# E6_main.net
KiCad netlist of a schematic drawn in EAGLE
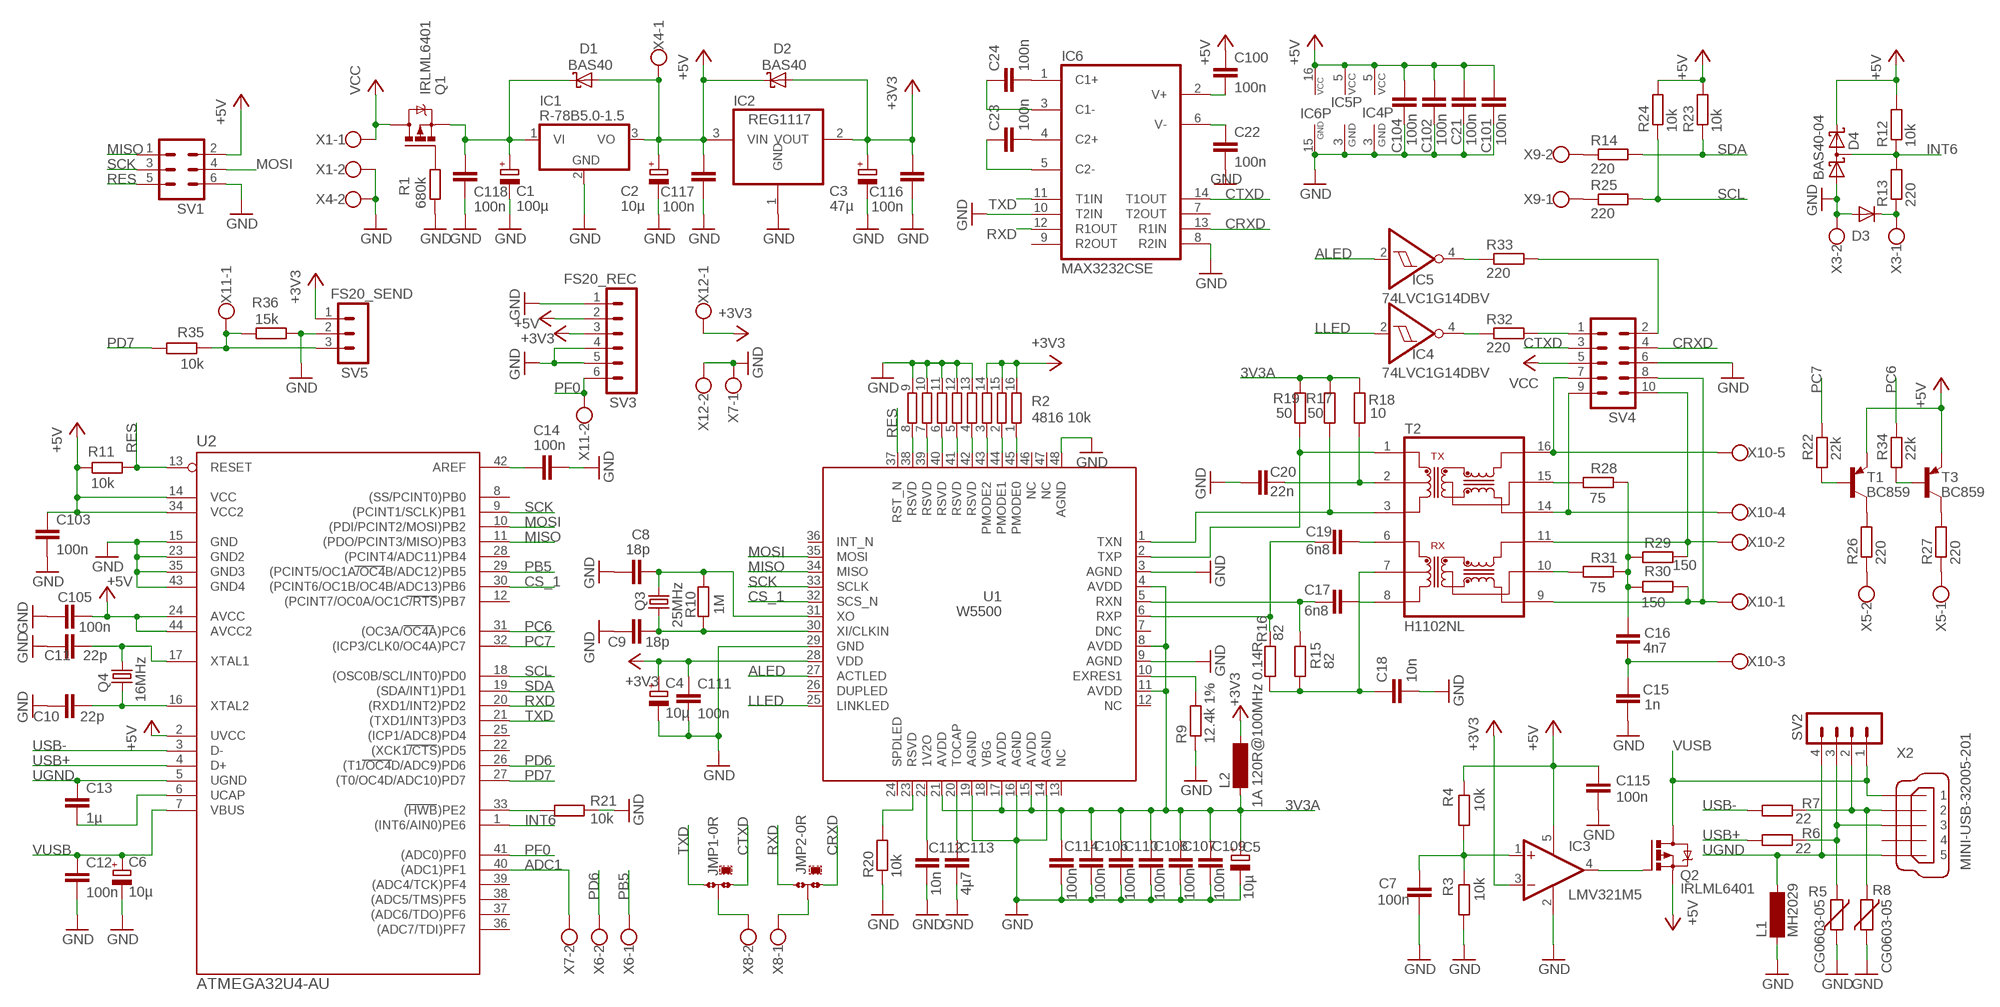
[diagram p0: schematic, sheet 1]

(export (version "E")
  (design (tool "Eeschema 10.0.6"))
  (components
    (comp (ref "C1")
      (value "100µ")
      (footprint "eagle-import:E2,5-7")
      (libsource (lib "eagle-import") (part "CPOL-EUE2.5-7"))
    )
    (comp (ref "C2")
      (value "10µ")
      (footprint "eagle-import:E2-5")
      (libsource (lib "eagle-import") (part "CPOL-EUE2-5"))
    )
    (comp (ref "C3")
      (value "47µ")
      (footprint "eagle-import:E2-5")
      (libsource (lib "eagle-import") (part "CPOL-EUE2-5"))
    )
    (comp (ref "C4")
      (value "10µ")
      (footprint "eagle-import:E2-5")
      (libsource (lib "eagle-import") (part "CPOL-EUE2-5"))
    )
    (comp (ref "C5")
      (value "10µ")
      (footprint "eagle-import:E2-5")
      (libsource (lib "eagle-import") (part "CPOL-EUE2-5"))
    )
    (comp (ref "C6")
      (value "10µ")
      (footprint "eagle-import:E2-5")
      (libsource (lib "eagle-import") (part "CPOL-EUE2-5"))
    )
    (comp (ref "C7")
      (value "100n")
      (footprint "eagle-import:C0805K")
      (libsource (lib "eagle-import") (part "C-EUC0805K"))
    )
    (comp (ref "C8")
      (value "18p")
      (footprint "eagle-import:C0805K")
      (libsource (lib "eagle-import") (part "C-EUC0805K"))
    )
    (comp (ref "C9")
      (value "18p")
      (footprint "eagle-import:C0805K")
      (libsource (lib "eagle-import") (part "C-EUC0805K"))
    )
    (comp (ref "C10")
      (value "22p")
      (footprint "eagle-import:C0805K")
      (libsource (lib "eagle-import") (part "C-EUC0805K"))
    )
    (comp (ref "C11")
      (value "22p")
      (footprint "eagle-import:C0805K")
      (libsource (lib "eagle-import") (part "C-EUC0805K"))
    )
    (comp (ref "C12")
      (value "100n")
      (footprint "eagle-import:C0805K")
      (libsource (lib "eagle-import") (part "C-EUC0805K"))
    )
    (comp (ref "C13")
      (value "1µ")
      (footprint "eagle-import:C0805K")
      (libsource (lib "eagle-import") (part "C-EUC0805K"))
    )
    (comp (ref "C14")
      (value "100n")
      (footprint "eagle-import:C0805K")
      (libsource (lib "eagle-import") (part "C-EUC0805K"))
    )
    (comp (ref "C15")
      (value "1n")
      (footprint "eagle-import:C0805K")
      (libsource (lib "eagle-import") (part "C-EUC0805K"))
    )
    (comp (ref "C16")
      (value "4n7")
      (footprint "eagle-import:C0805K")
      (libsource (lib "eagle-import") (part "C-EUC0805K"))
    )
    (comp (ref "C17")
      (value "6n8")
      (footprint "eagle-import:C0805K")
      (libsource (lib "eagle-import") (part "C-EUC0805K"))
    )
    (comp (ref "C18")
      (value "10n")
      (footprint "eagle-import:C0805K")
      (libsource (lib "eagle-import") (part "C-EUC0805K"))
    )
    (comp (ref "C19")
      (value "6n8")
      (footprint "eagle-import:C0805K")
      (libsource (lib "eagle-import") (part "C-EUC0805K"))
    )
    (comp (ref "C20")
      (value "22n")
      (footprint "eagle-import:C0805K")
      (libsource (lib "eagle-import") (part "C-EUC0805K"))
    )
    (comp (ref "C21")
      (value "100n")
      (footprint "eagle-import:C0805K")
      (libsource (lib "eagle-import") (part "C-EUC0805K"))
    )
    (comp (ref "C22")
      (value "100n")
      (footprint "eagle-import:C0805K")
      (libsource (lib "eagle-import") (part "C-EUC0805K"))
    )
    (comp (ref "C23")
      (value "100n")
      (footprint "eagle-import:C0805K")
      (libsource (lib "eagle-import") (part "C-EUC0805K"))
    )
    (comp (ref "C24")
      (value "100n")
      (footprint "eagle-import:C0805K")
      (libsource (lib "eagle-import") (part "C-EUC0805K"))
    )
    (comp (ref "C100")
      (value "100n")
      (footprint "eagle-import:C0805K")
      (libsource (lib "eagle-import") (part "C-EUC0805K"))
    )
    (comp (ref "C101")
      (value "100n")
      (footprint "eagle-import:C0805K")
      (libsource (lib "eagle-import") (part "C-EUC0805K"))
    )
    (comp (ref "C102")
      (value "100n")
      (footprint "eagle-import:C0805K")
      (libsource (lib "eagle-import") (part "C-EUC0805K"))
    )
    (comp (ref "C103")
      (value "100n")
      (footprint "eagle-import:C0805K")
      (libsource (lib "eagle-import") (part "C-EUC0805K"))
    )
    (comp (ref "C104")
      (value "100n")
      (footprint "eagle-import:C0805K")
      (libsource (lib "eagle-import") (part "C-EUC0805K"))
    )
    (comp (ref "C105")
      (value "100n")
      (footprint "eagle-import:C0805K")
      (libsource (lib "eagle-import") (part "C-EUC0805K"))
    )
    (comp (ref "C106")
      (value "100n")
      (footprint "eagle-import:C0805K")
      (libsource (lib "eagle-import") (part "C-EUC0805K"))
    )
    (comp (ref "C107")
      (value "100n")
      (footprint "eagle-import:C0805K")
      (libsource (lib "eagle-import") (part "C-EUC0805K"))
    )
    (comp (ref "C108")
      (value "100n")
      (footprint "eagle-import:C0805K")
      (libsource (lib "eagle-import") (part "C-EUC0805K"))
    )
    (comp (ref "C109")
      (value "100n")
      (footprint "eagle-import:C0805K")
      (libsource (lib "eagle-import") (part "C-EUC0805K"))
    )
    (comp (ref "C110")
      (value "100n")
      (footprint "eagle-import:C0805K")
      (libsource (lib "eagle-import") (part "C-EUC0805K"))
    )
    (comp (ref "C111")
      (value "100n")
      (footprint "eagle-import:C0805K")
      (libsource (lib "eagle-import") (part "C-EUC0805K"))
    )
    (comp (ref "C112")
      (value "10n")
      (footprint "eagle-import:C0805K")
      (libsource (lib "eagle-import") (part "C-EUC0805K"))
    )
    (comp (ref "C113")
      (value "4µ7")
      (footprint "eagle-import:C0805K")
      (libsource (lib "eagle-import") (part "C-EUC0805K"))
    )
    (comp (ref "C114")
      (value "100n")
      (footprint "eagle-import:C0805K")
      (libsource (lib "eagle-import") (part "C-EUC0805K"))
    )
    (comp (ref "C115")
      (value "100n")
      (footprint "eagle-import:C0805K")
      (libsource (lib "eagle-import") (part "C-EUC0805K"))
    )
    (comp (ref "C116")
      (value "100n")
      (footprint "eagle-import:C0805K")
      (libsource (lib "eagle-import") (part "C-EUC0805K"))
    )
    (comp (ref "C117")
      (value "100n")
      (footprint "eagle-import:C0805K")
      (libsource (lib "eagle-import") (part "C-EUC0805K"))
    )
    (comp (ref "C118")
      (value "100n")
      (footprint "eagle-import:C0805K")
      (libsource (lib "eagle-import") (part "C-EUC0805K"))
    )
    (comp (ref "D1")
      (value "BAS40")
      (footprint "eagle-import:SOT23")
      (libsource (lib "eagle-import") (part "BAS40"))
    )
    (comp (ref "D2")
      (value "BAS40")
      (footprint "eagle-import:SOT23")
      (libsource (lib "eagle-import") (part "BAS40"))
    )
    (comp (ref "D3")
      (value "DIODE-SOT54H")
      (footprint "eagle-import:SOT54H")
      (libsource (lib "eagle-import") (part "DIODE-SOT54H"))
    )
    (comp (ref "D4")
      (value "BAS40-04")
      (footprint "eagle-import:SOT23")
      (libsource (lib "eagle-import") (part "BAS40-04"))
    )
    (comp (ref "IC1")
      (value "R-78B5.0-1.5")
      (footprint "eagle-import:TO220V")
      (libsource (lib "eagle-import") (part "78TV05"))
    )
    (comp (ref "IC2")
      (value "REG1117")
      (footprint "eagle-import:SOT223")
      (libsource (lib "eagle-import") (part "REG1117"))
    )
    (comp (ref "IC3")
      (value "LMV321M5")
      (footprint "eagle-import:SOT23-5")
      (libsource (lib "eagle-import") (part "LMV321?M5"))
    )
    (comp (ref "IC4")
      (value "74LVC1G14DBV")
      (footprint "eagle-import:SOT23-5")
      (libsource (lib "eagle-import") (part "741G14DBVLVC"))
    )
    (comp (ref "IC5")
      (value "74LVC1G14DBV")
      (footprint "eagle-import:SOT23-5")
      (libsource (lib "eagle-import") (part "741G14DBVLVC"))
    )
    (comp (ref "IC6")
      (value "MAX3232CSE")
      (footprint "eagle-import:SO16")
      (libsource (lib "eagle-import") (part "MAX3232SEC"))
    )
    (comp (ref "JMP1")
      (value "0R-JUMPA")
      (footprint "eagle-import:A0R-JMP")
      (libsource (lib "eagle-import") (part "0R-JUMPA"))
    )
    (comp (ref "JMP2")
      (value "0R-JUMPA")
      (footprint "eagle-import:A0R-JMP")
      (libsource (lib "eagle-import") (part "0R-JUMPA"))
    )
    (comp (ref "L1")
      (value "MH2029")
      (footprint "eagle-import:SM-1206")
      (libsource (lib "eagle-import") (part "SM-1206"))
    )
    (comp (ref "L2")
      (value "1A 120R@100MHz 0.14R")
      (footprint "eagle-import:SM-1206")
      (libsource (lib "eagle-import") (part "SM-1206"))
    )
    (comp (ref "Q1")
      (value "IRLML6401")
      (footprint "eagle-import:MICRO3")
      (libsource (lib "eagle-import") (part "IRLML5203"))
    )
    (comp (ref "Q2")
      (value "IRLML6401")
      (footprint "eagle-import:MICRO3")
      (libsource (lib "eagle-import") (part "IRLML5203"))
    )
    (comp (ref "Q3")
      (value "25MHz")
      (footprint "eagle-import:HC49_S")
      (libsource (lib "eagle-import") (part "CRYSTALHC49S"))
    )
    (comp (ref "Q4")
      (value "16MHz")
      (footprint "eagle-import:HC49_S")
      (libsource (lib "eagle-import") (part "CRYSTALHC49S"))
    )
    (comp (ref "R1")
      (value "680k")
      (footprint "eagle-import:R0805")
      (libsource (lib "eagle-import") (part "R-EU_R0805"))
    )
    (comp (ref "R2")
      (value "4816 10k")
      (footprint "eagle-import:4816P")
      (fields (field (name "MF") "BOURNS, INC.") (field (name "MPN") "4816P-T01-684LF"))
      (libsource (lib "eagle-import") (part "4816P-T01"))
    )
    (comp (ref "R3")
      (value "10k")
      (footprint "eagle-import:R0805")
      (libsource (lib "eagle-import") (part "R-EU_R0805"))
    )
    (comp (ref "R4")
      (value "10k")
      (footprint "eagle-import:R0805")
      (libsource (lib "eagle-import") (part "R-EU_R0805"))
    )
    (comp (ref "R5")
      (value "CG0603-05")
      (footprint "eagle-import:CT_CN0603")
      (libsource (lib "eagle-import") (part "VARISTORCN0603"))
    )
    (comp (ref "R6")
      (value "22")
      (footprint "eagle-import:R0805")
      (libsource (lib "eagle-import") (part "R-EU_R0805"))
    )
    (comp (ref "R7")
      (value "22")
      (footprint "eagle-import:R0805")
      (libsource (lib "eagle-import") (part "R-EU_R0805"))
    )
    (comp (ref "R8")
      (value "CG0603-05")
      (footprint "eagle-import:CT_CN0603")
      (libsource (lib "eagle-import") (part "VARISTORCN0603"))
    )
    (comp (ref "R9")
      (value "12.4k 1%")
      (footprint "eagle-import:R0805")
      (libsource (lib "eagle-import") (part "R-EU_R0805"))
    )
    (comp (ref "R10")
      (value "1M")
      (footprint "eagle-import:R0805")
      (libsource (lib "eagle-import") (part "R-EU_R0805"))
    )
    (comp (ref "R11")
      (value "10k")
      (footprint "eagle-import:R0805")
      (libsource (lib "eagle-import") (part "R-EU_R0805"))
    )
    (comp (ref "R12")
      (value "10k")
      (footprint "eagle-import:R0805")
      (libsource (lib "eagle-import") (part "R-EU_R0805"))
    )
    (comp (ref "R13")
      (value "220")
      (footprint "eagle-import:R0805")
      (libsource (lib "eagle-import") (part "R-EU_R0805"))
    )
    (comp (ref "R14")
      (value "220")
      (footprint "eagle-import:R0805")
      (libsource (lib "eagle-import") (part "R-EU_R0805"))
    )
    (comp (ref "R15")
      (value "82")
      (footprint "eagle-import:R0805")
      (libsource (lib "eagle-import") (part "R-EU_R0805"))
    )
    (comp (ref "R16")
      (value "82")
      (footprint "eagle-import:R0805")
      (libsource (lib "eagle-import") (part "R-EU_R0805"))
    )
    (comp (ref "R17")
      (value "50")
      (footprint "eagle-import:R0805")
      (libsource (lib "eagle-import") (part "R-EU_R0805"))
    )
    (comp (ref "R18")
      (value "10")
      (footprint "eagle-import:R0805")
      (libsource (lib "eagle-import") (part "R-EU_R0805"))
    )
    (comp (ref "R19")
      (value "50")
      (footprint "eagle-import:R0805")
      (libsource (lib "eagle-import") (part "R-EU_R0805"))
    )
    (comp (ref "R20")
      (value "10k")
      (footprint "eagle-import:R0805")
      (libsource (lib "eagle-import") (part "R-EU_R0805"))
    )
    (comp (ref "R21")
      (value "10k")
      (footprint "eagle-import:R0805")
      (libsource (lib "eagle-import") (part "R-EU_R0805"))
    )
    (comp (ref "R22")
      (value "22k")
      (footprint "eagle-import:R0805")
      (libsource (lib "eagle-import") (part "R-EU_R0805"))
    )
    (comp (ref "R23")
      (value "10k")
      (footprint "eagle-import:R0805")
      (libsource (lib "eagle-import") (part "R-EU_R0805"))
    )
    (comp (ref "R24")
      (value "10k")
      (footprint "eagle-import:R0805")
      (libsource (lib "eagle-import") (part "R-EU_R0805"))
    )
    (comp (ref "R25")
      (value "220")
      (footprint "eagle-import:R0805")
      (libsource (lib "eagle-import") (part "R-EU_R0805"))
    )
    (comp (ref "R26")
      (value "220")
      (footprint "eagle-import:R0805")
      (libsource (lib "eagle-import") (part "R-EU_R0805"))
    )
    (comp (ref "R27")
      (value "220")
      (footprint "eagle-import:R0805")
      (libsource (lib "eagle-import") (part "R-EU_R0805"))
    )
    (comp (ref "R28")
      (value "75")
      (footprint "eagle-import:R0805")
      (libsource (lib "eagle-import") (part "R-EU_R0805"))
    )
    (comp (ref "R29")
      (value "150")
      (footprint "eagle-import:R0805")
      (libsource (lib "eagle-import") (part "R-EU_R0805"))
    )
    (comp (ref "R30")
      (value "150")
      (footprint "eagle-import:R0805")
      (libsource (lib "eagle-import") (part "R-EU_R0805"))
    )
    (comp (ref "R31")
      (value "75")
      (footprint "eagle-import:R0805")
      (libsource (lib "eagle-import") (part "R-EU_R0805"))
    )
    (comp (ref "R32")
      (value "220")
      (footprint "eagle-import:R0805")
      (libsource (lib "eagle-import") (part "R-EU_R0805"))
    )
    (comp (ref "R33")
      (value "220")
      (footprint "eagle-import:R0805")
      (libsource (lib "eagle-import") (part "R-EU_R0805"))
    )
    (comp (ref "R34")
      (value "22k")
      (footprint "eagle-import:R0805")
      (libsource (lib "eagle-import") (part "R-EU_R0805"))
    )
    (comp (ref "R35")
      (value "10k")
      (footprint "eagle-import:R0805")
      (libsource (lib "eagle-import") (part "R-EU_R0805"))
    )
    (comp (ref "R36")
      (value "15k")
      (footprint "eagle-import:R0805")
      (libsource (lib "eagle-import") (part "R-EU_R0805"))
    )
    (comp (ref "SV1")
      (value "ML6")
      (footprint "eagle-import:ML6")
      (libsource (lib "eagle-import") (part "ML6"))
    )
    (comp (ref "SV2")
      (value "MA04-1")
      (footprint "eagle-import:MA04-1")
      (libsource (lib "eagle-import") (part "MA04-1"))
    )
    (comp (ref "SV3")
      (value "FS20_REC")
      (footprint "eagle-import:MA06-1")
      (libsource (lib "eagle-import") (part "MA06-1"))
    )
    (comp (ref "SV4")
      (value "ML10")
      (footprint "eagle-import:ML10")
      (libsource (lib "eagle-import") (part "ML10"))
    )
    (comp (ref "SV5")
      (value "FS20_SEND")
      (footprint "eagle-import:MA03-1")
      (libsource (lib "eagle-import") (part "MA03-1"))
    )
    (comp (ref "T1")
      (value "BC859")
      (footprint "eagle-import:SOT23-BEC")
      (libsource (lib "eagle-import") (part "-PNP-SOT23-BECBC857A"))
    )
    (comp (ref "T2")
      (value "H1102NL")
      (footprint "eagle-import:HXXXX")
      (libsource (lib "eagle-import") (part "HX1188"))
    )
    (comp (ref "T3")
      (value "BC859")
      (footprint "eagle-import:SOT23-BEC")
      (libsource (lib "eagle-import") (part "-PNP-SOT23-BECBC857A"))
    )
    (comp (ref "U1")
      (value "W5500")
      (footprint "eagle-import:W5500")
      (libsource (lib "eagle-import") (part "W5500"))
    )
    (comp (ref "U2")
      (value "ATMEGA32U4-AU")
      (footprint "eagle-import:TQFP44")
      (libsource (lib "eagle-import") (part "ATMEGA32U4-AU"))
    )
    (comp (ref "X1")
      (value "W237-02P")
      (footprint "eagle-import:W237-132")
      (libsource (lib "eagle-import") (part "W237-02P"))
    )
    (comp (ref "X2")
      (value "MINI-USB-32005-201")
      (footprint "eagle-import:32005-201")
      (libsource (lib "eagle-import") (part "MINI-USB-32005-201"))
    )
    (comp (ref "X3")
      (value "W237-02P")
      (footprint "eagle-import:W237-132")
      (libsource (lib "eagle-import") (part "W237-02P"))
    )
    (comp (ref "X4")
      (value "W237-02P")
      (footprint "eagle-import:W237-132")
      (libsource (lib "eagle-import") (part "W237-02P"))
    )
    (comp (ref "X5")
      (value "W237-02P")
      (footprint "eagle-import:W237-132")
      (libsource (lib "eagle-import") (part "W237-02P"))
    )
    (comp (ref "X6")
      (value "W237-02P")
      (footprint "eagle-import:W237-132")
      (libsource (lib "eagle-import") (part "W237-02P"))
    )
    (comp (ref "X7")
      (value "W237-02P")
      (footprint "eagle-import:W237-132")
      (libsource (lib "eagle-import") (part "W237-02P"))
    )
    (comp (ref "X8")
      (value "W237-02P")
      (footprint "eagle-import:W237-132")
      (libsource (lib "eagle-import") (part "W237-02P"))
    )
    (comp (ref "X9")
      (value "W237-02P")
      (footprint "eagle-import:W237-132")
      (libsource (lib "eagle-import") (part "W237-02P"))
    )
    (comp (ref "X10")
      (value "W237-05P")
      (footprint "eagle-import:W237-5P")
      (libsource (lib "eagle-import") (part "W237-05P"))
    )
    (comp (ref "X11")
      (value "W237-02P")
      (footprint "eagle-import:W237-132")
      (libsource (lib "eagle-import") (part "W237-02P"))
    )
    (comp (ref "X12")
      (value "W237-02P")
      (footprint "eagle-import:W237-132")
      (libsource (lib "eagle-import") (part "W237-02P"))
    )
  )
  (nets
    (net (code "1") (name "+3V3") (class "Default")
      (node (ref "C111") (pin "1") (pinfunction "1_1") (pintype "passive"))
      (node (ref "C116") (pin "2") (pinfunction "2_2") (pintype "passive"))
      (node (ref "C3") (pin "+") (pinfunction "+_+") (pintype "passive"))
      (node (ref "C4") (pin "+") (pinfunction "+_+") (pintype "passive"))
      (node (ref "D2") (pin "1") (pinfunction "A_1") (pintype "passive"))
      (node (ref "IC2") (pin "2") (pinfunction "VOUT_2") (pintype "output"))
      (node (ref "IC3") (pin "3") (pinfunction "-IN_3") (pintype "input"))
      (node (ref "L2") (pin "2") (pinfunction "2_2") (pintype "passive"))
      (node (ref "R2") (pin "14") (pinfunction "14_14") (pintype "passive"))
      (node (ref "R2") (pin "15") (pinfunction "15_15") (pintype "passive"))
      (node (ref "R2") (pin "16") (pinfunction "16_16") (pintype "passive"))
      (node (ref "SV3") (pin "3") (pinfunction "3_3") (pintype "passive"))
      (node (ref "SV5") (pin "1") (pinfunction "1_1") (pintype "passive"))
      (node (ref "U1") (pin "28") (pinfunction "VDD_28") (pintype "passive"))
      (node (ref "X12") (pin "1") (pinfunction "KL_1") (pintype "passive"))
    )
    (net (code "2") (name "+5V") (class "Default")
      (node (ref "C100") (pin "1") (pinfunction "1_1") (pintype "passive"))
      (node (ref "C101") (pin "1") (pinfunction "1_1") (pintype "passive"))
      (node (ref "C102") (pin "2") (pinfunction "2_2") (pintype "passive"))
      (node (ref "C103") (pin "1") (pinfunction "1_1") (pintype "passive"))
      (node (ref "C104") (pin "2") (pinfunction "2_2") (pintype "passive"))
      (node (ref "C105") (pin "1") (pinfunction "1_1") (pintype "passive"))
      (node (ref "C115") (pin "2") (pinfunction "2_2") (pintype "passive"))
      (node (ref "C117") (pin "2") (pinfunction "2_2") (pintype "passive"))
      (node (ref "C2") (pin "+") (pinfunction "+_+") (pintype "passive"))
      (node (ref "C21") (pin "1") (pinfunction "1_1") (pintype "passive"))
      (node (ref "D1") (pin "1") (pinfunction "A_1") (pintype "passive"))
      (node (ref "D2") (pin "3") (pinfunction "C_3") (pintype "passive"))
      (node (ref "D4") (pin "2") (pinfunction "C2_2") (pintype "passive"))
      (node (ref "IC1") (pin "3") (pinfunction "VO_3") (pintype "passive"))
      (node (ref "IC2") (pin "3") (pinfunction "VIN_3") (pintype "input"))
      (node (ref "IC3") (pin "5") (pinfunction "V+_5") (pintype "power_in"))
      (node (ref "IC4") (pin "5") (pinfunction "VCC_5") (pintype "power_in"))
      (node (ref "IC5") (pin "5") (pinfunction "VCC_5") (pintype "power_in"))
      (node (ref "IC6") (pin "16") (pinfunction "VCC_16") (pintype "power_in"))
      (node (ref "Q2") (pin "2") (pinfunction "S_2") (pintype "passive"))
      (node (ref "R11") (pin "2") (pinfunction "2_2") (pintype "passive"))
      (node (ref "R12") (pin "2") (pinfunction "2_2") (pintype "passive"))
      (node (ref "R23") (pin "2") (pinfunction "2_2") (pintype "passive"))
      (node (ref "R24") (pin "2") (pinfunction "2_2") (pintype "passive"))
      (node (ref "R4") (pin "1") (pinfunction "1_1") (pintype "passive"))
      (node (ref "SV1") (pin "2") (pinfunction "2_2") (pintype "passive"))
      (node (ref "SV3") (pin "2") (pinfunction "2_2") (pintype "passive"))
      (node (ref "T1") (pin "E") (pinfunction "E_E") (pintype "passive"))
      (node (ref "T3") (pin "E") (pinfunction "E_E") (pintype "passive"))
      (node (ref "U2") (pin "14") (pinfunction "VCC_14") (pintype "bidirectional"))
      (node (ref "U2") (pin "2") (pinfunction "UVCC_2") (pintype "bidirectional"))
      (node (ref "U2") (pin "24") (pinfunction "AVCC_24") (pintype "bidirectional"))
      (node (ref "U2") (pin "34") (pinfunction "VCC2_34") (pintype "bidirectional"))
      (node (ref "U2") (pin "44") (pinfunction "AVCC2_44") (pintype "bidirectional"))
      (node (ref "X4") (pin "1") (pinfunction "KL_1") (pintype "passive"))
    )
    (net (code "3") (name "/3V3A") (class "Default")
      (node (ref "C106") (pin "1") (pinfunction "1_1") (pintype "passive"))
      (node (ref "C107") (pin "1") (pinfunction "1_1") (pintype "passive"))
      (node (ref "C108") (pin "1") (pinfunction "1_1") (pintype "passive"))
      (node (ref "C109") (pin "1") (pinfunction "1_1") (pintype "passive"))
      (node (ref "C110") (pin "1") (pinfunction "1_1") (pintype "passive"))
      (node (ref "C114") (pin "1") (pinfunction "1_1") (pintype "passive"))
      (node (ref "C5") (pin "+") (pinfunction "+_+") (pintype "passive"))
      (node (ref "L2") (pin "1") (pinfunction "1_1") (pintype "passive"))
      (node (ref "R17") (pin "2") (pinfunction "2_2") (pintype "passive"))
      (node (ref "R18") (pin "2") (pinfunction "2_2") (pintype "passive"))
      (node (ref "R19") (pin "2") (pinfunction "2_2") (pintype "passive"))
      (node (ref "U1") (pin "11") (pinfunction "AVDD_11") (pintype "passive"))
      (node (ref "U1") (pin "15") (pinfunction "AVDD_15") (pintype "passive"))
      (node (ref "U1") (pin "17") (pinfunction "AVDD_17") (pintype "passive"))
      (node (ref "U1") (pin "21") (pinfunction "AVDD_21") (pintype "passive"))
      (node (ref "U1") (pin "4") (pinfunction "AVDD_4") (pintype "passive"))
      (node (ref "U1") (pin "8") (pinfunction "AVDD_8") (pintype "passive"))
    )
    (net (code "4") (name "/ADC1") (class "Default")
      (node (ref "U2") (pin "40") (pinfunction "(ADC1)PF1_40") (pintype "bidirectional"))
      (node (ref "X7") (pin "2") (pinfunction "KL_2") (pintype "passive"))
    )
    (net (code "5") (name "/ALED") (class "Default")
      (node (ref "IC5") (pin "2") (pinfunction "I_2") (pintype "input"))
      (node (ref "U1") (pin "27") (pinfunction "ACTLED_27") (pintype "passive"))
    )
    (net (code "6") (name "/CRXD") (class "Default")
      (node (ref "IC6") (pin "13") (pinfunction "R1IN_13") (pintype "input"))
      (node (ref "JMP2") (pin "1") (pinfunction "1_1") (pintype "passive"))
      (node (ref "SV4") (pin "4") (pinfunction "4_4") (pintype "passive"))
    )
    (net (code "7") (name "/CS_1") (class "Default")
      (node (ref "U1") (pin "32") (pinfunction "SCS_N_32") (pintype "passive"))
      (node (ref "U2") (pin "30") (pinfunction "(PCINT6/OC1B/OC4B/ADC13)PB6_30") (pintype "bidirectional"))
    )
    (net (code "8") (name "/CTXD") (class "Default")
      (node (ref "IC6") (pin "14") (pinfunction "T1OUT_14") (pintype "output"))
      (node (ref "JMP1") (pin "1") (pinfunction "1_1") (pintype "passive"))
      (node (ref "SV4") (pin "3") (pinfunction "3_3") (pintype "passive"))
    )
    (net (code "9") (name "/INT6") (class "Default")
      (node (ref "D4") (pin "3") (pinfunction "C1A2_3") (pintype "passive"))
      (node (ref "R12") (pin "1") (pinfunction "1_1") (pintype "passive"))
      (node (ref "R13") (pin "2") (pinfunction "2_2") (pintype "passive"))
      (node (ref "U2") (pin "1") (pinfunction "(INT6/AIN0)PE6_1") (pintype "bidirectional"))
    )
    (net (code "10") (name "/LLED") (class "Default")
      (node (ref "IC4") (pin "2") (pinfunction "I_2") (pintype "input"))
      (node (ref "U1") (pin "25") (pinfunction "LINKLED_25") (pintype "passive"))
    )
    (net (code "11") (name "/MISO") (class "Default")
      (node (ref "SV1") (pin "1") (pinfunction "1_1") (pintype "passive"))
      (node (ref "U1") (pin "34") (pinfunction "MISO_34") (pintype "passive"))
      (node (ref "U2") (pin "11") (pinfunction "(PDO/PCINT3/MISO)PB3_11") (pintype "bidirectional"))
    )
    (net (code "12") (name "/MOSI") (class "Default")
      (node (ref "SV1") (pin "4") (pinfunction "4_4") (pintype "passive"))
      (node (ref "U1") (pin "35") (pinfunction "MOSI_35") (pintype "passive"))
      (node (ref "U2") (pin "10") (pinfunction "(PDI/PCINT2/MOSI)PB2_10") (pintype "bidirectional"))
    )
    (net (code "13") (name "/PB5") (class "Default")
      (node (ref "U2") (pin "29") (pinfunction "(PCINT5/OC1A/OC4B/ADC12)PB5_29") (pintype "bidirectional"))
      (node (ref "X6") (pin "1") (pinfunction "KL_1") (pintype "passive"))
    )
    (net (code "14") (name "/PC6") (class "Default")
      (node (ref "R34") (pin "2") (pinfunction "2_2") (pintype "passive"))
      (node (ref "U2") (pin "31") (pinfunction "(OC3A/OC4A)PC6_31") (pintype "bidirectional"))
    )
    (net (code "15") (name "/PC7") (class "Default")
      (node (ref "R22") (pin "2") (pinfunction "2_2") (pintype "passive"))
      (node (ref "U2") (pin "32") (pinfunction "(ICP3/CLK0/OC4A)PC7_32") (pintype "bidirectional"))
    )
    (net (code "16") (name "/PD6") (class "Default")
      (node (ref "U2") (pin "26") (pinfunction "(T1/OC4D/ADC9)PD6_26") (pintype "bidirectional"))
      (node (ref "X6") (pin "2") (pinfunction "KL_2") (pintype "passive"))
    )
    (net (code "17") (name "/PD7") (class "Default")
      (node (ref "R35") (pin "2") (pinfunction "2_2") (pintype "passive"))
      (node (ref "U2") (pin "27") (pinfunction "(T0/OC4D/ADC10)PD7_27") (pintype "bidirectional"))
    )
    (net (code "18") (name "/PF0") (class "Default")
      (node (ref "SV3") (pin "6") (pinfunction "6_6") (pintype "passive"))
      (node (ref "U2") (pin "41") (pinfunction "(ADC0)PF0_41") (pintype "bidirectional"))
      (node (ref "X11") (pin "2") (pinfunction "KL_2") (pintype "passive"))
    )
    (net (code "19") (name "/RES") (class "Default")
      (node (ref "R11") (pin "1") (pinfunction "1_1") (pintype "passive"))
      (node (ref "SV1") (pin "5") (pinfunction "5_5") (pintype "passive"))
      (node (ref "U1") (pin "37") (pinfunction "RST_N_37") (pintype "passive"))
      (node (ref "U2") (pin "13") (pinfunction "RESET_13") (pintype "bidirectional"))
    )
    (net (code "20") (name "/RXD") (class "Default")
      (node (ref "IC6") (pin "12") (pinfunction "R1OUT_12") (pintype "output"))
      (node (ref "JMP2") (pin "3") (pinfunction "3_3") (pintype "passive"))
      (node (ref "U2") (pin "20") (pinfunction "(RXD1/INT2)PD2_20") (pintype "bidirectional"))
    )
    (net (code "21") (name "/SCK") (class "Default")
      (node (ref "SV1") (pin "3") (pinfunction "3_3") (pintype "passive"))
      (node (ref "U1") (pin "33") (pinfunction "SCLK_33") (pintype "passive"))
      (node (ref "U2") (pin "9") (pinfunction "(PCINT1/SCLK)PB1_9") (pintype "bidirectional"))
    )
    (net (code "22") (name "/SCL") (class "Default")
      (node (ref "R24") (pin "1") (pinfunction "1_1") (pintype "passive"))
      (node (ref "R25") (pin "2") (pinfunction "2_2") (pintype "passive"))
      (node (ref "U2") (pin "18") (pinfunction "(OSC0B/SCL/INT0)PD0_18") (pintype "bidirectional"))
    )
    (net (code "23") (name "/SDA") (class "Default")
      (node (ref "R14") (pin "2") (pinfunction "2_2") (pintype "passive"))
      (node (ref "R23") (pin "1") (pinfunction "1_1") (pintype "passive"))
      (node (ref "U2") (pin "19") (pinfunction "(SDA/INT1)PD1_19") (pintype "bidirectional"))
    )
    (net (code "24") (name "/TXD") (class "Default")
      (node (ref "IC6") (pin "11") (pinfunction "T1IN_11") (pintype "input"))
      (node (ref "JMP1") (pin "3") (pinfunction "3_3") (pintype "passive"))
      (node (ref "U2") (pin "21") (pinfunction "(TXD1/INT3)PD3_21") (pintype "bidirectional"))
    )
    (net (code "25") (name "/UGND") (class "Default")
      (node (ref "C13") (pin "1") (pinfunction "1_1") (pintype "passive"))
      (node (ref "L1") (pin "2") (pinfunction "2_2") (pintype "passive"))
      (node (ref "SV2") (pin "4") (pinfunction "4_4") (pintype "passive"))
      (node (ref "U2") (pin "5") (pinfunction "UGND_5") (pintype "bidirectional"))
      (node (ref "X2") (pin "5") (pinfunction "5_5") (pintype "passive"))
    )
    (net (code "26") (name "/USB+") (class "Default")
      (node (ref "R6") (pin "2") (pinfunction "2_2") (pintype "passive"))
      (node (ref "U2") (pin "4") (pinfunction "D+_4") (pintype "bidirectional"))
    )
    (net (code "27") (name "/USB-") (class "Default")
      (node (ref "R7") (pin "2") (pinfunction "2_2") (pintype "passive"))
      (node (ref "U2") (pin "3") (pinfunction "D-_3") (pintype "bidirectional"))
    )
    (net (code "28") (name "/VUSB") (class "Default")
      (node (ref "C12") (pin "1") (pinfunction "1_1") (pintype "passive"))
      (node (ref "C6") (pin "+") (pinfunction "+_+") (pintype "passive"))
      (node (ref "Q2") (pin "3") (pinfunction "D_3") (pintype "passive"))
      (node (ref "SV2") (pin "1") (pinfunction "1_1") (pintype "passive"))
      (node (ref "U2") (pin "7") (pinfunction "VBUS_7") (pintype "bidirectional"))
      (node (ref "X2") (pin "1") (pinfunction "1_1") (pintype "passive"))
    )
    (net (code "29") (name "GND") (class "Default")
      (node (ref "C1") (pin "-") (pinfunction "-_-") (pintype "passive"))
      (node (ref "C10") (pin "2") (pinfunction "2_2") (pintype "passive"))
      (node (ref "C101") (pin "2") (pinfunction "2_2") (pintype "passive"))
      (node (ref "C102") (pin "1") (pinfunction "1_1") (pintype "passive"))
      (node (ref "C103") (pin "2") (pinfunction "2_2") (pintype "passive"))
      (node (ref "C104") (pin "1") (pinfunction "1_1") (pintype "passive"))
      (node (ref "C105") (pin "2") (pinfunction "2_2") (pintype "passive"))
      (node (ref "C106") (pin "2") (pinfunction "2_2") (pintype "passive"))
      (node (ref "C107") (pin "2") (pinfunction "2_2") (pintype "passive"))
      (node (ref "C108") (pin "2") (pinfunction "2_2") (pintype "passive"))
      (node (ref "C109") (pin "2") (pinfunction "2_2") (pintype "passive"))
      (node (ref "C11") (pin "1") (pinfunction "1_1") (pintype "passive"))
      (node (ref "C110") (pin "2") (pinfunction "2_2") (pintype "passive"))
      (node (ref "C111") (pin "2") (pinfunction "2_2") (pintype "passive"))
      (node (ref "C112") (pin "2") (pinfunction "2_2") (pintype "passive"))
      (node (ref "C113") (pin "2") (pinfunction "2_2") (pintype "passive"))
      (node (ref "C114") (pin "2") (pinfunction "2_2") (pintype "passive"))
      (node (ref "C115") (pin "1") (pinfunction "1_1") (pintype "passive"))
      (node (ref "C116") (pin "1") (pinfunction "1_1") (pintype "passive"))
      (node (ref "C117") (pin "1") (pinfunction "1_1") (pintype "passive"))
      (node (ref "C118") (pin "2") (pinfunction "2_2") (pintype "passive"))
      (node (ref "C12") (pin "2") (pinfunction "2_2") (pintype "passive"))
      (node (ref "C14") (pin "2") (pinfunction "2_2") (pintype "passive"))
      (node (ref "C15") (pin "1") (pinfunction "1_1") (pintype "passive"))
      (node (ref "C18") (pin "2") (pinfunction "2_2") (pintype "passive"))
      (node (ref "C2") (pin "-") (pinfunction "-_-") (pintype "passive"))
      (node (ref "C20") (pin "1") (pinfunction "1_1") (pintype "passive"))
      (node (ref "C21") (pin "2") (pinfunction "2_2") (pintype "passive"))
      (node (ref "C22") (pin "2") (pinfunction "2_2") (pintype "passive"))
      (node (ref "C3") (pin "-") (pinfunction "-_-") (pintype "passive"))
      (node (ref "C4") (pin "-") (pinfunction "-_-") (pintype "passive"))
      (node (ref "C5") (pin "-") (pinfunction "-_-") (pintype "passive"))
      (node (ref "C6") (pin "-") (pinfunction "-_-") (pintype "passive"))
      (node (ref "C7") (pin "2") (pinfunction "2_2") (pintype "passive"))
      (node (ref "C8") (pin "1") (pinfunction "1_1") (pintype "passive"))
      (node (ref "C9") (pin "2") (pinfunction "2_2") (pintype "passive"))
      (node (ref "D3") (pin "A") (pinfunction "A_A") (pintype "passive"))
      (node (ref "D4") (pin "1") (pinfunction "A1_1") (pintype "passive"))
      (node (ref "IC1") (pin "2") (pinfunction "GND_2") (pintype "passive"))
      (node (ref "IC2") (pin "1") (pinfunction "GND_1") (pintype "power_in"))
      (node (ref "IC3") (pin "2") (pinfunction "V-_2") (pintype "power_in"))
      (node (ref "IC4") (pin "3") (pinfunction "GND_3") (pintype "power_in"))
      (node (ref "IC5") (pin "3") (pinfunction "GND_3") (pintype "power_in"))
      (node (ref "IC6") (pin "10") (pinfunction "T2IN_10") (pintype "input"))
      (node (ref "IC6") (pin "15") (pinfunction "GND_15") (pintype "power_in"))
      (node (ref "IC6") (pin "8") (pinfunction "R2IN_8") (pintype "input"))
      (node (ref "L1") (pin "1") (pinfunction "1_1") (pintype "passive"))
      (node (ref "R1") (pin "2") (pinfunction "2_2") (pintype "passive"))
      (node (ref "R2") (pin "10") (pinfunction "10_10") (pintype "passive"))
      (node (ref "R2") (pin "11") (pinfunction "11_11") (pintype "passive"))
      (node (ref "R2") (pin "12") (pinfunction "12_12") (pintype "passive"))
      (node (ref "R2") (pin "13") (pinfunction "13_13") (pintype "passive"))
      (node (ref "R2") (pin "9") (pinfunction "9_9") (pintype "passive"))
      (node (ref "R20") (pin "1") (pinfunction "1_1") (pintype "passive"))
      (node (ref "R21") (pin "2") (pinfunction "2_2") (pintype "passive"))
      (node (ref "R3") (pin "2") (pinfunction "2_2") (pintype "passive"))
      (node (ref "R36") (pin "1") (pinfunction "1_1") (pintype "passive"))
      (node (ref "R5") (pin "2") (pinfunction "2_2") (pintype "passive"))
      (node (ref "R8") (pin "2") (pinfunction "2_2") (pintype "passive"))
      (node (ref "R9") (pin "1") (pinfunction "1_1") (pintype "passive"))
      (node (ref "SV1") (pin "6") (pinfunction "6_6") (pintype "passive"))
      (node (ref "SV3") (pin "1") (pinfunction "1_1") (pintype "passive"))
      (node (ref "SV3") (pin "4") (pinfunction "4_4") (pintype "passive"))
      (node (ref "SV3") (pin "5") (pinfunction "5_5") (pintype "passive"))
      (node (ref "SV4") (pin "6") (pinfunction "6_6") (pintype "passive"))
      (node (ref "SV5") (pin "2") (pinfunction "2_2") (pintype "passive"))
      (node (ref "U1") (pin "14") (pinfunction "AGND_14") (pintype "passive"))
      (node (ref "U1") (pin "16") (pinfunction "AGND_16") (pintype "passive"))
      (node (ref "U1") (pin "19") (pinfunction "AGND_19") (pintype "passive"))
      (node (ref "U1") (pin "29") (pinfunction "GND_29") (pintype "passive"))
      (node (ref "U1") (pin "3") (pinfunction "AGND_3") (pintype "passive"))
      (node (ref "U1") (pin "48") (pinfunction "AGND_48") (pintype "passive"))
      (node (ref "U1") (pin "9") (pinfunction "AGND_9") (pintype "passive"))
      (node (ref "U2") (pin "15") (pinfunction "GND_15") (pintype "bidirectional"))
      (node (ref "U2") (pin "23") (pinfunction "GND2_23") (pintype "bidirectional"))
      (node (ref "U2") (pin "35") (pinfunction "GND3_35") (pintype "bidirectional"))
      (node (ref "U2") (pin "43") (pinfunction "GND4_43") (pintype "bidirectional"))
      (node (ref "X1") (pin "2") (pinfunction "KL_2") (pintype "passive"))
      (node (ref "X12") (pin "2") (pinfunction "KL_2") (pintype "passive"))
      (node (ref "X3") (pin "2") (pinfunction "KL_2") (pintype "passive"))
      (node (ref "X4") (pin "2") (pinfunction "KL_2") (pintype "passive"))
      (node (ref "X7") (pin "1") (pinfunction "KL_1") (pintype "passive"))
    )
    (net (code "30") (name "Net-(C16-Pad2)") (class "Default")
      (node (ref "C16") (pin "2") (pinfunction "2_2") (pintype "passive"))
      (node (ref "R28") (pin "1") (pinfunction "1_1") (pintype "passive"))
      (node (ref "R29") (pin "2") (pinfunction "2_2") (pintype "passive"))
      (node (ref "R30") (pin "2") (pinfunction "2_2") (pintype "passive"))
      (node (ref "R31") (pin "1") (pinfunction "1_1") (pintype "passive"))
    )
    (net (code "31") (name "Net-(C17-Pad2)") (class "Default")
      (node (ref "C17") (pin "2") (pinfunction "2_2") (pintype "passive"))
      (node (ref "T2") (pin "8") (pinfunction "8_8") (pintype "passive"))
    )
    (net (code "32") (name "Net-(C18-Pad1)") (class "Default")
      (node (ref "C18") (pin "1") (pinfunction "1_1") (pintype "passive"))
      (node (ref "R15") (pin "2") (pinfunction "2_2") (pintype "passive"))
      (node (ref "R16") (pin "2") (pinfunction "2_2") (pintype "passive"))
      (node (ref "T2") (pin "7") (pinfunction "7_7") (pintype "passive"))
    )
    (net (code "33") (name "Net-(C19-Pad2)") (class "Default")
      (node (ref "C19") (pin "2") (pinfunction "2_2") (pintype "passive"))
      (node (ref "T2") (pin "6") (pinfunction "6_6") (pintype "passive"))
    )
    (net (code "34") (name "Net-(C20-Pad2)") (class "Default")
      (node (ref "C20") (pin "2") (pinfunction "2_2") (pintype "passive"))
      (node (ref "R18") (pin "1") (pinfunction "1_1") (pintype "passive"))
      (node (ref "T2") (pin "2") (pinfunction "2_2") (pintype "passive"))
    )
    (net (code "35") (name "Net-(D1-C)") (class "Default")
      (node (ref "C1") (pin "+") (pinfunction "+_+") (pintype "passive"))
      (node (ref "C118") (pin "1") (pinfunction "1_1") (pintype "passive"))
      (node (ref "D1") (pin "3") (pinfunction "C_3") (pintype "passive"))
      (node (ref "IC1") (pin "1") (pinfunction "VI_1") (pintype "input"))
      (node (ref "Q1") (pin "2") (pinfunction "S_2") (pintype "passive"))
    )
    (net (code "36") (name "Net-(IC3-+IN)") (class "Default")
      (node (ref "C7") (pin "1") (pinfunction "1_1") (pintype "passive"))
      (node (ref "IC3") (pin "1") (pinfunction "+IN_1") (pintype "input"))
      (node (ref "R3") (pin "1") (pinfunction "1_1") (pintype "passive"))
      (node (ref "R4") (pin "2") (pinfunction "2_2") (pintype "passive"))
    )
    (net (code "37") (name "Net-(IC3-OUT)") (class "Default")
      (node (ref "IC3") (pin "4") (pinfunction "OUT_4") (pintype "output"))
      (node (ref "Q2") (pin "1") (pinfunction "G_1") (pintype "passive"))
    )
    (net (code "38") (name "Net-(IC4A-O)") (class "Default")
      (node (ref "IC4") (pin "4") (pinfunction "O_4") (pintype "output"))
      (node (ref "R32") (pin "1") (pinfunction "1_1") (pintype "passive"))
    )
    (net (code "39") (name "Net-(IC5A-O)") (class "Default")
      (node (ref "IC5") (pin "4") (pinfunction "O_4") (pintype "output"))
      (node (ref "R33") (pin "1") (pinfunction "1_1") (pintype "passive"))
    )
    (net (code "40") (name "Net-(IC6A-C1+)") (class "Default")
      (node (ref "C24") (pin "2") (pinfunction "2_2") (pintype "passive"))
      (node (ref "IC6") (pin "1") (pinfunction "C1+_1") (pintype "bidirectional"))
    )
    (net (code "41") (name "Net-(IC6A-C1-)") (class "Default")
      (node (ref "C24") (pin "1") (pinfunction "1_1") (pintype "passive"))
      (node (ref "IC6") (pin "3") (pinfunction "C1-_3") (pintype "bidirectional"))
    )
    (net (code "42") (name "Net-(IC6A-C2+)") (class "Default")
      (node (ref "C23") (pin "2") (pinfunction "2_2") (pintype "passive"))
      (node (ref "IC6") (pin "4") (pinfunction "C2+_4") (pintype "bidirectional"))
    )
    (net (code "43") (name "Net-(IC6A-C2-)") (class "Default")
      (node (ref "C23") (pin "1") (pinfunction "1_1") (pintype "passive"))
      (node (ref "IC6") (pin "5") (pinfunction "C2-_5") (pintype "bidirectional"))
    )
    (net (code "44") (name "Net-(IC6A-V+)") (class "Default")
      (node (ref "C100") (pin "2") (pinfunction "2_2") (pintype "passive"))
      (node (ref "IC6") (pin "2") (pinfunction "V+_2") (pintype "bidirectional"))
    )
    (net (code "45") (name "Net-(IC6A-V-)") (class "Default")
      (node (ref "C22") (pin "1") (pinfunction "1_1") (pintype "passive"))
      (node (ref "IC6") (pin "6") (pinfunction "V-_6") (pintype "bidirectional"))
    )
    (net (code "46") (name "Net-(Q1-G)") (class "Default")
      (node (ref "Q1") (pin "1") (pinfunction "G_1") (pintype "passive"))
      (node (ref "R1") (pin "1") (pinfunction "1_1") (pintype "passive"))
    )
    (net (code "47") (name "Net-(R2-Pad4)") (class "Default")
      (node (ref "R2") (pin "4") (pinfunction "4_4") (pintype "passive"))
      (node (ref "U1") (pin "42") (pinfunction "RSVD_42") (pintype "passive"))
    )
    (net (code "48") (name "Net-(R2-Pad5)") (class "Default")
      (node (ref "R2") (pin "5") (pinfunction "5_5") (pintype "passive"))
      (node (ref "U1") (pin "41") (pinfunction "RSVD_41") (pintype "passive"))
    )
    (net (code "49") (name "Net-(R2-Pad6)") (class "Default")
      (node (ref "R2") (pin "6") (pinfunction "6_6") (pintype "passive"))
      (node (ref "U1") (pin "40") (pinfunction "RSVD_40") (pintype "passive"))
    )
    (net (code "50") (name "Net-(R2-Pad7)") (class "Default")
      (node (ref "R2") (pin "7") (pinfunction "7_7") (pintype "passive"))
      (node (ref "U1") (pin "39") (pinfunction "RSVD_39") (pintype "passive"))
    )
    (net (code "51") (name "Net-(R2-Pad8)") (class "Default")
      (node (ref "R2") (pin "8") (pinfunction "8_8") (pintype "passive"))
      (node (ref "U1") (pin "38") (pinfunction "RSVD_38") (pintype "passive"))
    )
    (net (code "52") (name "Net-(R5-Pad1)") (class "Default")
      (node (ref "R5") (pin "1") (pinfunction "1_1") (pintype "passive"))
      (node (ref "R6") (pin "1") (pinfunction "1_1") (pintype "passive"))
      (node (ref "SV2") (pin "3") (pinfunction "3_3") (pintype "passive"))
      (node (ref "X2") (pin "3") (pinfunction "3_3") (pintype "passive"))
    )
    (net (code "53") (name "Net-(R7-Pad1)") (class "Default")
      (node (ref "R7") (pin "1") (pinfunction "1_1") (pintype "passive"))
      (node (ref "R8") (pin "1") (pinfunction "1_1") (pintype "passive"))
      (node (ref "SV2") (pin "2") (pinfunction "2_2") (pintype "passive"))
      (node (ref "X2") (pin "2") (pinfunction "2_2") (pintype "passive"))
    )
    (net (code "54") (name "Net-(R20-Pad2)") (class "Default")
      (node (ref "R20") (pin "2") (pinfunction "2_2") (pintype "passive"))
      (node (ref "U1") (pin "23") (pinfunction "RSVD_23") (pintype "passive"))
    )
    (net (code "55") (name "Net-(R22-Pad1)") (class "Default")
      (node (ref "R22") (pin "1") (pinfunction "1_1") (pintype "passive"))
      (node (ref "T1") (pin "B") (pinfunction "B_B") (pintype "passive"))
    )
    (net (code "56") (name "Net-(R26-Pad2)") (class "Default")
      (node (ref "R26") (pin "2") (pinfunction "2_2") (pintype "passive"))
      (node (ref "T1") (pin "C") (pinfunction "C_C") (pintype "passive"))
    )
    (net (code "57") (name "Net-(R27-Pad2)") (class "Default")
      (node (ref "R27") (pin "2") (pinfunction "2_2") (pintype "passive"))
      (node (ref "T3") (pin "C") (pinfunction "C_C") (pintype "passive"))
    )
    (net (code "58") (name "Net-(R28-Pad2)") (class "Default")
      (node (ref "R28") (pin "2") (pinfunction "2_2") (pintype "passive"))
      (node (ref "T2") (pin "15") (pinfunction "15_15") (pintype "passive"))
    )
    (net (code "59") (name "Net-(R31-Pad2)") (class "Default")
      (node (ref "R31") (pin "2") (pinfunction "2_2") (pintype "passive"))
      (node (ref "T2") (pin "10") (pinfunction "10_10") (pintype "passive"))
    )
    (net (code "60") (name "Net-(R32-Pad2)") (class "Default")
      (node (ref "R32") (pin "2") (pinfunction "2_2") (pintype "passive"))
      (node (ref "SV4") (pin "1") (pinfunction "1_1") (pintype "passive"))
    )
    (net (code "61") (name "Net-(R33-Pad2)") (class "Default")
      (node (ref "R33") (pin "2") (pinfunction "2_2") (pintype "passive"))
      (node (ref "SV4") (pin "2") (pinfunction "2_2") (pintype "passive"))
    )
    (net (code "62") (name "Net-(R34-Pad1)") (class "Default")
      (node (ref "R34") (pin "1") (pinfunction "1_1") (pintype "passive"))
      (node (ref "T3") (pin "B") (pinfunction "B_B") (pintype "passive"))
    )
    (net (code "63") (name "Net-(U1-1V2O)") (class "Default")
      (node (ref "C112") (pin "1") (pinfunction "1_1") (pintype "passive"))
      (node (ref "U1") (pin "22") (pinfunction "1V2O_22") (pintype "passive"))
    )
    (net (code "64") (name "Net-(U1-EXRES1)") (class "Default")
      (node (ref "R9") (pin "2") (pinfunction "2_2") (pintype "passive"))
      (node (ref "U1") (pin "10") (pinfunction "EXRES1_10") (pintype "passive"))
    )
    (net (code "65") (name "Net-(U1-PMODE0)") (class "Default")
      (node (ref "R2") (pin "1") (pinfunction "1_1") (pintype "passive"))
      (node (ref "U1") (pin "45") (pinfunction "PMODE0_45") (pintype "passive"))
    )
    (net (code "66") (name "Net-(U1-PMODE1)") (class "Default")
      (node (ref "R2") (pin "2") (pinfunction "2_2") (pintype "passive"))
      (node (ref "U1") (pin "44") (pinfunction "PMODE1_44") (pintype "passive"))
    )
    (net (code "67") (name "Net-(U1-PMODE2)") (class "Default")
      (node (ref "R2") (pin "3") (pinfunction "3_3") (pintype "passive"))
      (node (ref "U1") (pin "43") (pinfunction "PMODE2_43") (pintype "passive"))
    )
    (net (code "68") (name "Net-(U1-RXN)") (class "Default")
      (node (ref "C17") (pin "1") (pinfunction "1_1") (pintype "passive"))
      (node (ref "R15") (pin "1") (pinfunction "1_1") (pintype "passive"))
      (node (ref "U1") (pin "5") (pinfunction "RXN_5") (pintype "passive"))
    )
    (net (code "69") (name "Net-(U1-RXP)") (class "Default")
      (node (ref "C19") (pin "1") (pinfunction "1_1") (pintype "passive"))
      (node (ref "R16") (pin "1") (pinfunction "1_1") (pintype "passive"))
      (node (ref "U1") (pin "6") (pinfunction "RXP_6") (pintype "passive"))
    )
    (net (code "70") (name "Net-(U1-TOCAP)") (class "Default")
      (node (ref "C113") (pin "1") (pinfunction "1_1") (pintype "passive"))
      (node (ref "U1") (pin "20") (pinfunction "TOCAP_20") (pintype "passive"))
    )
    (net (code "71") (name "Net-(U1-TXN)") (class "Default")
      (node (ref "R17") (pin "1") (pinfunction "1_1") (pintype "passive"))
      (node (ref "T2") (pin "3") (pinfunction "3_3") (pintype "passive"))
      (node (ref "U1") (pin "1") (pinfunction "TXN_1") (pintype "passive"))
    )
    (net (code "72") (name "Net-(U1-TXP)") (class "Default")
      (node (ref "R19") (pin "1") (pinfunction "1_1") (pintype "passive"))
      (node (ref "T2") (pin "1") (pinfunction "1_1") (pintype "passive"))
      (node (ref "U1") (pin "2") (pinfunction "TXP_2") (pintype "passive"))
    )
    (net (code "73") (name "Net-(U1-XI{slash}CLKIN)") (class "Default")
      (node (ref "C9") (pin "1") (pinfunction "1_1") (pintype "passive"))
      (node (ref "Q3") (pin "2") (pinfunction "2_2") (pintype "passive"))
      (node (ref "R10") (pin "2") (pinfunction "2_2") (pintype "passive"))
      (node (ref "U1") (pin "30") (pinfunction "XI/CLKIN_30") (pintype "passive"))
    )
    (net (code "74") (name "Net-(U1-XO)") (class "Default")
      (node (ref "C8") (pin "2") (pinfunction "2_2") (pintype "passive"))
      (node (ref "Q3") (pin "1") (pinfunction "1_1") (pintype "passive"))
      (node (ref "R10") (pin "1") (pinfunction "1_1") (pintype "passive"))
      (node (ref "U1") (pin "31") (pinfunction "XO_31") (pintype "passive"))
    )
    (net (code "75") (name "Net-(U2-(HWB)PE2)") (class "Default")
      (node (ref "R21") (pin "1") (pinfunction "1_1") (pintype "passive"))
      (node (ref "U2") (pin "33") (pinfunction "(HWB)PE2_33") (pintype "bidirectional"))
    )
    (net (code "76") (name "Net-(U2-AREF)") (class "Default")
      (node (ref "C14") (pin "1") (pinfunction "1_1") (pintype "passive"))
      (node (ref "U2") (pin "42") (pinfunction "AREF_42") (pintype "bidirectional"))
    )
    (net (code "77") (name "Net-(U2-UCAP)") (class "Default")
      (node (ref "C13") (pin "2") (pinfunction "2_2") (pintype "passive"))
      (node (ref "U2") (pin "6") (pinfunction "UCAP_6") (pintype "bidirectional"))
    )
    (net (code "78") (name "Net-(U2-XTAL1)") (class "Default")
      (node (ref "C11") (pin "2") (pinfunction "2_2") (pintype "passive"))
      (node (ref "Q4") (pin "1") (pinfunction "1_1") (pintype "passive"))
      (node (ref "U2") (pin "17") (pinfunction "XTAL1_17") (pintype "bidirectional"))
    )
    (net (code "79") (name "Net-(U2-XTAL2)") (class "Default")
      (node (ref "C10") (pin "1") (pinfunction "1_1") (pintype "passive"))
      (node (ref "Q4") (pin "2") (pinfunction "2_2") (pintype "passive"))
      (node (ref "U2") (pin "16") (pinfunction "XTAL2_16") (pintype "bidirectional"))
    )
    (net (code "80") (name "Net-(X3A-KL)") (class "Default")
      (node (ref "D3") (pin "C") (pinfunction "C_C") (pintype "passive"))
      (node (ref "R13") (pin "1") (pinfunction "1_1") (pintype "passive"))
      (node (ref "X3") (pin "1") (pinfunction "KL_1") (pintype "passive"))
    )
    (net (code "81") (name "Net-(X5A-KL)") (class "Default")
      (node (ref "R27") (pin "1") (pinfunction "1_1") (pintype "passive"))
      (node (ref "X5") (pin "1") (pinfunction "KL_1") (pintype "passive"))
    )
    (net (code "82") (name "Net-(X5B-KL)") (class "Default")
      (node (ref "R26") (pin "1") (pinfunction "1_1") (pintype "passive"))
      (node (ref "X5") (pin "2") (pinfunction "KL_2") (pintype "passive"))
    )
    (net (code "83") (name "Net-(X8A-KL)") (class "Default")
      (node (ref "JMP2") (pin "2") (pinfunction "2_2") (pintype "passive"))
      (node (ref "X8") (pin "1") (pinfunction "KL_1") (pintype "passive"))
    )
    (net (code "84") (name "Net-(X8B-KL)") (class "Default")
      (node (ref "JMP1") (pin "2") (pinfunction "2_2") (pintype "passive"))
      (node (ref "X8") (pin "2") (pinfunction "KL_2") (pintype "passive"))
    )
    (net (code "85") (name "Net-(X9A-KL)") (class "Default")
      (node (ref "R25") (pin "1") (pinfunction "1_1") (pintype "passive"))
      (node (ref "X9") (pin "1") (pinfunction "KL_1") (pintype "passive"))
    )
    (net (code "86") (name "Net-(X9B-KL)") (class "Default")
      (node (ref "R14") (pin "1") (pinfunction "1_1") (pintype "passive"))
      (node (ref "X9") (pin "2") (pinfunction "KL_2") (pintype "passive"))
    )
    (net (code "87") (name "Net-(X10A-KL)") (class "Default")
      (node (ref "R30") (pin "1") (pinfunction "1_1") (pintype "passive"))
      (node (ref "SV4") (pin "8") (pinfunction "8_8") (pintype "passive"))
      (node (ref "T2") (pin "9") (pinfunction "9_9") (pintype "passive"))
      (node (ref "X10") (pin "1") (pinfunction "KL_1") (pintype "passive"))
    )
    (net (code "88") (name "Net-(X10B-KL)") (class "Default")
      (node (ref "R29") (pin "1") (pinfunction "1_1") (pintype "passive"))
      (node (ref "SV4") (pin "10") (pinfunction "10_10") (pintype "passive"))
      (node (ref "T2") (pin "11") (pinfunction "11_11") (pintype "passive"))
      (node (ref "X10") (pin "2") (pinfunction "KL_2") (pintype "passive"))
    )
    (net (code "89") (name "Net-(X10C-KL)") (class "Default")
      (node (ref "C15") (pin "2") (pinfunction "2_2") (pintype "passive"))
      (node (ref "C16") (pin "1") (pinfunction "1_1") (pintype "passive"))
      (node (ref "X10") (pin "3") (pinfunction "KL_3") (pintype "passive"))
    )
    (net (code "90") (name "Net-(X10D-KL)") (class "Default")
      (node (ref "SV4") (pin "9") (pinfunction "9_9") (pintype "passive"))
      (node (ref "T2") (pin "14") (pinfunction "14_14") (pintype "passive"))
      (node (ref "X10") (pin "4") (pinfunction "KL_4") (pintype "passive"))
    )
    (net (code "91") (name "Net-(X10E-KL)") (class "Default")
      (node (ref "SV4") (pin "7") (pinfunction "7_7") (pintype "passive"))
      (node (ref "T2") (pin "16") (pinfunction "16_16") (pintype "passive"))
      (node (ref "X10") (pin "5") (pinfunction "KL_5") (pintype "passive"))
    )
    (net (code "92") (name "Net-(X11A-KL)") (class "Default")
      (node (ref "R35") (pin "1") (pinfunction "1_1") (pintype "passive"))
      (node (ref "R36") (pin "2") (pinfunction "2_2") (pintype "passive"))
      (node (ref "SV5") (pin "3") (pinfunction "3_3") (pintype "passive"))
      (node (ref "X11") (pin "1") (pinfunction "KL_1") (pintype "passive"))
    )
    (net (code "93") (name "VCC") (class "Default")
      (node (ref "Q1") (pin "3") (pinfunction "D_3") (pintype "passive"))
      (node (ref "SV4") (pin "5") (pinfunction "5_5") (pintype "passive"))
      (node (ref "X1") (pin "1") (pinfunction "KL_1") (pintype "passive"))
    )
    (net (code "94") (name "unconnected-(IC6A-R2OUT-Pad9)") (class "Default")
      (node (ref "IC6") (pin "9") (pinfunction "R2OUT_9") (pintype "output"))
    )
    (net (code "95") (name "unconnected-(IC6A-T2OUT-Pad7)") (class "Default")
      (node (ref "IC6") (pin "7") (pinfunction "T2OUT_7") (pintype "output"))
    )
    (net (code "96") (name "unconnected-(U1-DNC-Pad7)") (class "Default")
      (node (ref "U1") (pin "7") (pinfunction "DNC_7") (pintype "passive"))
    )
    (net (code "97") (name "unconnected-(U1-DUPLED-Pad26)") (class "Default")
      (node (ref "U1") (pin "26") (pinfunction "DUPLED_26") (pintype "passive"))
    )
    (net (code "98") (name "unconnected-(U1-INT_N-Pad36)") (class "Default")
      (node (ref "U1") (pin "36") (pinfunction "INT_N_36") (pintype "passive"))
    )
    (net (code "99") (name "unconnected-(U1-NC-Pad12)") (class "Default")
      (node (ref "U1") (pin "12") (pinfunction "NC_12") (pintype "passive"))
    )
    (net (code "100") (name "unconnected-(U1-NC-Pad13)") (class "Default")
      (node (ref "U1") (pin "13") (pinfunction "NC_13") (pintype "passive"))
    )
    (net (code "101") (name "unconnected-(U1-NC-Pad46)") (class "Default")
      (node (ref "U1") (pin "46") (pinfunction "NC_46") (pintype "passive"))
    )
    (net (code "102") (name "unconnected-(U1-NC-Pad47)") (class "Default")
      (node (ref "U1") (pin "47") (pinfunction "NC_47") (pintype "passive"))
    )
    (net (code "103") (name "unconnected-(U1-SPDLED-Pad24)") (class "Default")
      (node (ref "U1") (pin "24") (pinfunction "SPDLED_24") (pintype "passive"))
    )
    (net (code "104") (name "unconnected-(U1-VBG-Pad18)") (class "Default")
      (node (ref "U1") (pin "18") (pinfunction "VBG_18") (pintype "passive"))
    )
    (net (code "105") (name "unconnected-(U2-(ADC4{slash}TCK)PF4-Pad39)") (class "Default")
      (node (ref "U2") (pin "39") (pinfunction "(ADC4/TCK)PF4_39") (pintype "bidirectional"))
    )
    (net (code "106") (name "unconnected-(U2-(ADC5{slash}TMS)PF5-Pad38)") (class "Default")
      (node (ref "U2") (pin "38") (pinfunction "(ADC5/TMS)PF5_38") (pintype "bidirectional"))
    )
    (net (code "107") (name "unconnected-(U2-(ADC6{slash}TDO)PF6-Pad37)") (class "Default")
      (node (ref "U2") (pin "37") (pinfunction "(ADC6/TDO)PF6_37") (pintype "bidirectional"))
    )
    (net (code "108") (name "unconnected-(U2-(ADC7{slash}TDI)PF7-Pad36)") (class "Default")
      (node (ref "U2") (pin "36") (pinfunction "(ADC7/TDI)PF7_36") (pintype "bidirectional"))
    )
    (net (code "109") (name "unconnected-(U2-(ICP1{slash}ADC8)PD4-Pad25)") (class "Default")
      (node (ref "U2") (pin "25") (pinfunction "(ICP1/ADC8)PD4_25") (pintype "bidirectional"))
    )
    (net (code "110") (name "unconnected-(U2-(PCINT4{slash}ADC11)PB4-Pad28)") (class "Default")
      (node (ref "U2") (pin "28") (pinfunction "(PCINT4/ADC11)PB4_28") (pintype "bidirectional"))
    )
    (net (code "111") (name "unconnected-(U2-(PCINT7{slash}OC0A{slash}OC1C{slash}RTS)PB7-Pad12)") (class "Default")
      (node (ref "U2") (pin "12") (pinfunction "(PCINT7/OC0A/OC1C/RTS)PB7_12") (pintype "bidirectional"))
    )
    (net (code "112") (name "unconnected-(U2-(SS{slash}PCINT0)PB0-Pad8)") (class "Default")
      (node (ref "U2") (pin "8") (pinfunction "(SS/PCINT0)PB0_8") (pintype "bidirectional"))
    )
    (net (code "113") (name "unconnected-(U2-(XCK1{slash}CTS)PD5-Pad22)") (class "Default")
      (node (ref "U2") (pin "22") (pinfunction "(XCK1/CTS)PD5_22") (pintype "bidirectional"))
    )
    (net (code "114") (name "unconnected-(X2-Pad4)") (class "Default")
      (node (ref "X2") (pin "4") (pinfunction "4_4") (pintype "passive"))
    )
  )
)
